# band4_1.net
KiCad netlist of a schematic drawn in EAGLE
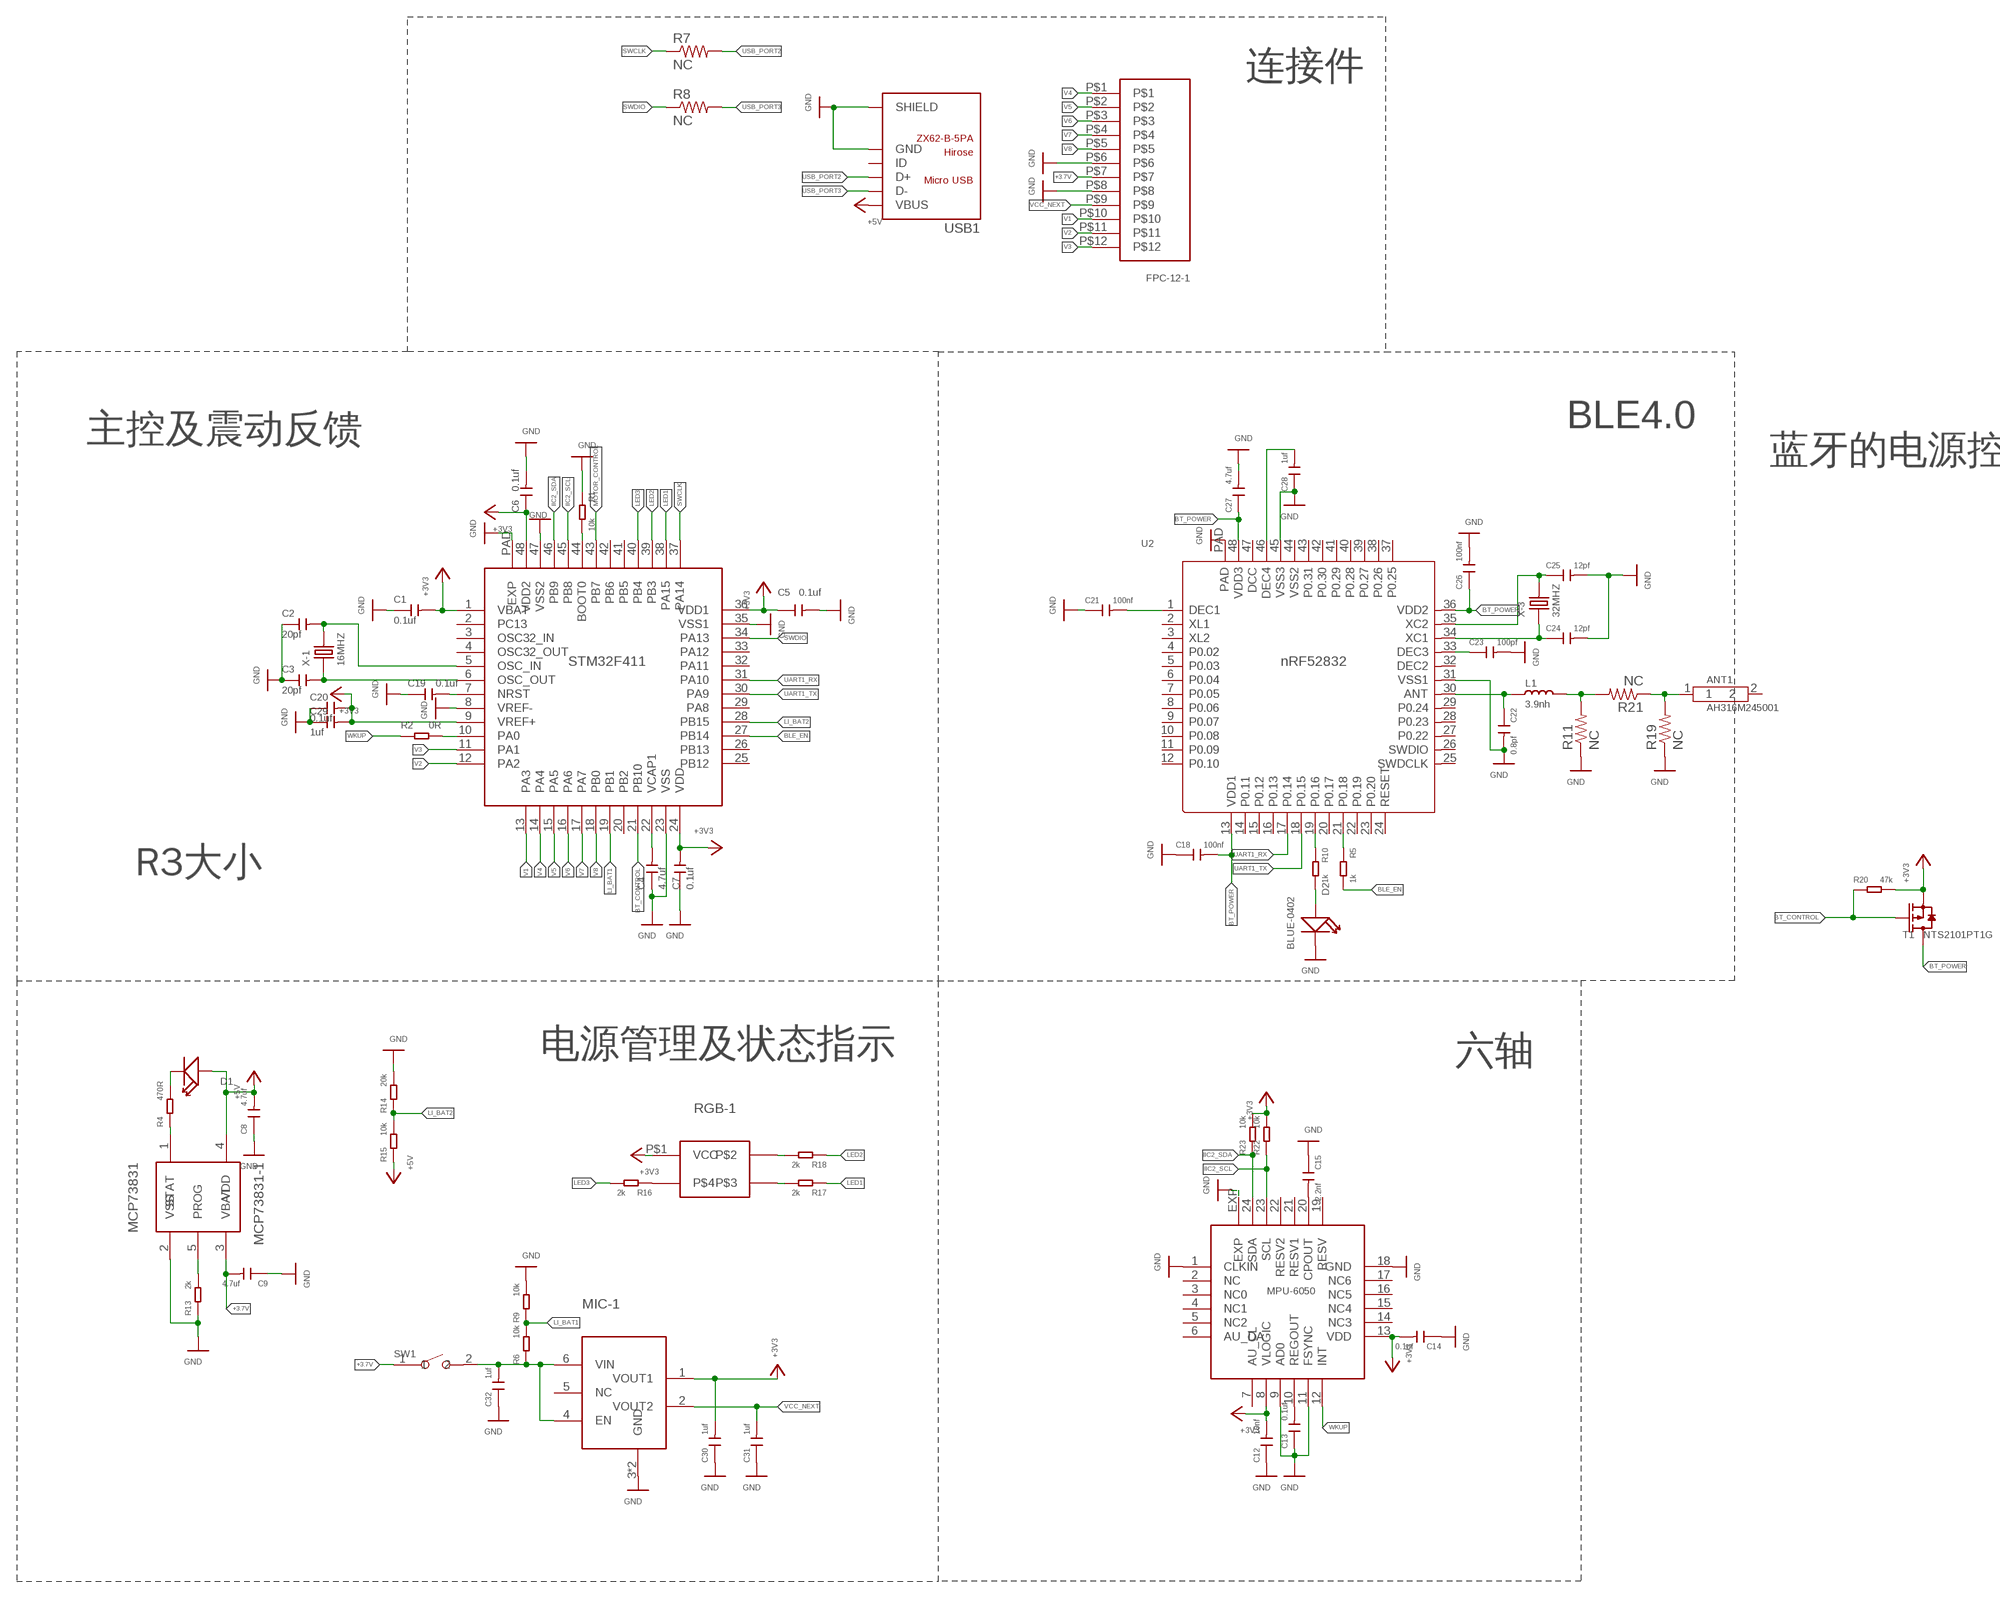
[diagram p0: schematic, sheet 1]

(export (version "E")
  (design (tool "Eeschema 10.0.6"))
  (components
    (comp (ref "ANT1")
      (value "AH316M245001")
      (footprint "eagle-import:ANT2-SMD-3.2X1.6X0.5MM")
      (fields (field (name "MPN") "AH316M245001-T"))
      (libsource (lib "eagle-import") (part "ANTENNA-2.4GHZ-AH316M245001-T"))
    )
    (comp (ref "C1")
      (value "0.1uf")
      (footprint "eagle-import:C0402")
      (fields (field (name "MPN") "CC0402BRNPO9BNR50"))
      (libsource (lib "eagle-import") (part "C(0402)"))
    )
    (comp (ref "C2")
      (value "20pf")
      (footprint "eagle-import:C0402")
      (fields (field (name "MPN") "CC0402BRNPO9BNR50"))
      (libsource (lib "eagle-import") (part "C(0402)"))
    )
    (comp (ref "C3")
      (value "20pf")
      (footprint "eagle-import:C0402")
      (fields (field (name "MPN") "CC0402BRNPO9BNR50"))
      (libsource (lib "eagle-import") (part "C(0402)"))
    )
    (comp (ref "C4")
      (value "4.7uf")
      (footprint "eagle-import:C0402")
      (fields (field (name "MPN") "CC0402BRNPO9BNR50"))
      (libsource (lib "eagle-import") (part "C(0402)"))
    )
    (comp (ref "C5")
      (value "0.1uf")
      (footprint "eagle-import:C0402")
      (fields (field (name "MPN") "CC0402BRNPO9BNR50"))
      (libsource (lib "eagle-import") (part "C(0402)"))
    )
    (comp (ref "C6")
      (value "0.1uf")
      (footprint "eagle-import:C0402")
      (fields (field (name "MPN") "CC0402BRNPO9BNR50"))
      (libsource (lib "eagle-import") (part "C(0402)"))
    )
    (comp (ref "C7")
      (value "0.1uf")
      (footprint "eagle-import:C0402")
      (fields (field (name "MPN") "CC0402BRNPO9BNR50"))
      (libsource (lib "eagle-import") (part "C(0402)"))
    )
    (comp (ref "C8")
      (value "4.7uf")
      (footprint "eagle-import:C0402")
      (fields (field (name "MPN") "CC0402BRNPO9BNR50"))
      (libsource (lib "eagle-import") (part "C(0402)"))
    )
    (comp (ref "C9")
      (value "4.7uf")
      (footprint "eagle-import:C0402")
      (fields (field (name "MPN") "CC0402BRNPO9BNR50"))
      (libsource (lib "eagle-import") (part "C(0402)"))
    )
    (comp (ref "C12")
      (value "10nf")
      (footprint "eagle-import:C0402")
      (fields (field (name "MPN") "CC0402BRNPO9BNR50"))
      (libsource (lib "eagle-import") (part "C(0402)"))
    )
    (comp (ref "C13")
      (value "0.1uf")
      (footprint "eagle-import:C0402")
      (fields (field (name "MPN") "CC0402BRNPO9BNR50"))
      (libsource (lib "eagle-import") (part "C(0402)"))
    )
    (comp (ref "C14")
      (value "0.1uf")
      (footprint "eagle-import:C0402")
      (fields (field (name "MPN") "CC0402BRNPO9BNR50"))
      (libsource (lib "eagle-import") (part "C(0402)"))
    )
    (comp (ref "C15")
      (value "2.2nf")
      (footprint "eagle-import:C0402")
      (fields (field (name "MPN") "CC0402BRNPO9BNR50"))
      (libsource (lib "eagle-import") (part "C(0402)"))
    )
    (comp (ref "C18")
      (value "100nf")
      (footprint "eagle-import:C0402")
      (fields (field (name "MPN") "CC0402BRNPO9BNR50"))
      (libsource (lib "eagle-import") (part "C(0402)"))
    )
    (comp (ref "C19")
      (value "0.1uf")
      (footprint "eagle-import:C0402")
      (fields (field (name "MPN") "CC0402BRNPO9BNR50"))
      (libsource (lib "eagle-import") (part "C(0402)"))
    )
    (comp (ref "C20")
      (value "0.1uf")
      (footprint "eagle-import:C0402")
      (fields (field (name "MPN") "CC0402BRNPO9BNR50"))
      (libsource (lib "eagle-import") (part "C(0402)"))
    )
    (comp (ref "C21")
      (value "100nf")
      (footprint "eagle-import:C0402")
      (fields (field (name "MPN") "CC0402BRNPO9BNR50"))
      (libsource (lib "eagle-import") (part "C(0402)"))
    )
    (comp (ref "C22")
      (value "0.8pf")
      (footprint "eagle-import:C0402")
      (fields (field (name "MPN") "CC0402BRNPO9BNR50"))
      (libsource (lib "eagle-import") (part "C(0402)"))
    )
    (comp (ref "C23")
      (value "100pf")
      (footprint "eagle-import:C0402")
      (fields (field (name "MPN") "CC0402BRNPO9BNR50"))
      (libsource (lib "eagle-import") (part "C(0402)"))
    )
    (comp (ref "C24")
      (value "12pf")
      (footprint "eagle-import:C0402")
      (fields (field (name "MPN") "CC0402BRNPO9BNR50"))
      (libsource (lib "eagle-import") (part "C(0402)"))
    )
    (comp (ref "C25")
      (value "12pf")
      (footprint "eagle-import:C0402")
      (fields (field (name "MPN") "CC0402BRNPO9BNR50"))
      (libsource (lib "eagle-import") (part "C(0402)"))
    )
    (comp (ref "C26")
      (value "100nf")
      (footprint "eagle-import:C0402")
      (fields (field (name "MPN") "CC0402BRNPO9BNR50"))
      (libsource (lib "eagle-import") (part "C(0402)"))
    )
    (comp (ref "C27")
      (value "4.7uf")
      (footprint "eagle-import:C0402")
      (fields (field (name "MPN") "CC0402BRNPO9BNR50"))
      (libsource (lib "eagle-import") (part "C(0402)"))
    )
    (comp (ref "C28")
      (value "1uf")
      (footprint "eagle-import:C0402")
      (fields (field (name "MPN") "CC0402BRNPO9BNR50"))
      (libsource (lib "eagle-import") (part "C(0402)"))
    )
    (comp (ref "C29")
      (value "1uf")
      (footprint "eagle-import:C0402")
      (fields (field (name "MPN") "CC0402BRNPO9BNR50"))
      (libsource (lib "eagle-import") (part "C(0402)"))
    )
    (comp (ref "C30")
      (value "1uf")
      (footprint "eagle-import:C0402")
      (fields (field (name "MPN") "CC0402BRNPO9BNR50"))
      (libsource (lib "eagle-import") (part "C(0402)"))
    )
    (comp (ref "C31")
      (value "1uf")
      (footprint "eagle-import:C0402")
      (fields (field (name "MPN") "CC0402BRNPO9BNR50"))
      (libsource (lib "eagle-import") (part "C(0402)"))
    )
    (comp (ref "C32")
      (value "1uf")
      (footprint "eagle-import:C0402")
      (fields (field (name "MPN") "CC0402BRNPO9BNR50"))
      (libsource (lib "eagle-import") (part "C(0402)"))
    )
    (comp (ref "D1")
      (value "LED-(0402)")
      (footprint "eagle-import:LED-0402")
      (fields (field (name "MPN") "BL-HB337A-AV-TRB"))
      (libsource (lib "eagle-import") (part "LED-(0402)"))
    )
    (comp (ref "D2")
      (value "BLUE-0402")
      (footprint "eagle-import:LED-0402")
      (fields (field (name "MPN") "BL-HB337A-AV-TRB"))
      (libsource (lib "eagle-import") (part "LED-(0402)"))
    )
    (comp (ref "FPC-12-1")
      (value "FPC-12")
      (footprint "eagle-import:FPC-12")
      (libsource (lib "eagle-import") (part "FPC-12"))
    )
    (comp (ref "L1")
      (value "3.9nh")
      (footprint "eagle-import:L0402")
      (libsource (lib "eagle-import") (part "INDUCTOR(0402)"))
    )
    (comp (ref "MCP73831-1")
      (value "MCP73831")
      (footprint "eagle-import:SOT23-5")
      (libsource (lib "eagle-import") (part "MCP73831"))
    )
    (comp (ref "MCU-1")
      (value "STM32F411")
      (footprint "eagle-import:QFN48G-0.5-7X7MM")
      (libsource (lib "eagle-import") (part "STM32F411"))
    )
    (comp (ref "MIC-1")
      (value "MIC5528")
      (footprint "eagle-import:THIN-DFN")
      (libsource (lib "eagle-import") (part "MIC5528"))
    )
    (comp (ref "MPU6050-1")
      (value "MPU-6050")
      (footprint "eagle-import:QFN24-4X4")
      (libsource (lib "eagle-import") (part "MPU-6050"))
    )
    (comp (ref "R1")
      (value "10k")
      (footprint "eagle-import:R0402")
      (fields (field (name "MPN") "RC0402JR-070RL"))
      (libsource (lib "eagle-import") (part "RES-(0402)"))
    )
    (comp (ref "R2")
      (value "0R")
      (footprint "eagle-import:R0402")
      (fields (field (name "MPN") "RC0402JR-070RL"))
      (libsource (lib "eagle-import") (part "RES-(0402)"))
    )
    (comp (ref "R4")
      (value "470R")
      (footprint "eagle-import:R0402")
      (fields (field (name "MPN") "RC0402JR-070RL"))
      (libsource (lib "eagle-import") (part "RES-(0402)"))
    )
    (comp (ref "R5")
      (value "1k")
      (footprint "eagle-import:R0402")
      (fields (field (name "MPN") "RC0402JR-070RL"))
      (libsource (lib "eagle-import") (part "RES-(0402)"))
    )
    (comp (ref "R6")
      (value "10k")
      (footprint "eagle-import:R0402")
      (fields (field (name "MPN") "RC0402JR-070RL"))
      (libsource (lib "eagle-import") (part "RES-(0402)"))
    )
    (comp (ref "R7")
      (value "NC")
      (footprint "eagle-import:0201")
      (libsource (lib "eagle-import") (part "R_0201"))
    )
    (comp (ref "R8")
      (value "NC")
      (footprint "eagle-import:0201")
      (libsource (lib "eagle-import") (part "R_0201"))
    )
    (comp (ref "R9")
      (value "10k")
      (footprint "eagle-import:R0402")
      (fields (field (name "MPN") "RC0402JR-070RL"))
      (libsource (lib "eagle-import") (part "RES-(0402)"))
    )
    (comp (ref "R10")
      (value "1k")
      (footprint "eagle-import:R0402")
      (fields (field (name "MPN") "RC0402JR-070RL"))
      (libsource (lib "eagle-import") (part "RES-(0402)"))
    )
    (comp (ref "R11")
      (value "NC")
      (footprint "eagle-import:0201")
      (libsource (lib "eagle-import") (part "R_0201"))
    )
    (comp (ref "R13")
      (value "2k")
      (footprint "eagle-import:R0402")
      (fields (field (name "MPN") "RC0402JR-070RL"))
      (libsource (lib "eagle-import") (part "RES-(0402)"))
    )
    (comp (ref "R14")
      (value "20k")
      (footprint "eagle-import:R0402")
      (fields (field (name "MPN") "RC0402JR-070RL"))
      (libsource (lib "eagle-import") (part "RES-(0402)"))
    )
    (comp (ref "R15")
      (value "10k")
      (footprint "eagle-import:R0402")
      (fields (field (name "MPN") "RC0402JR-070RL"))
      (libsource (lib "eagle-import") (part "RES-(0402)"))
    )
    (comp (ref "R16")
      (value "2k")
      (footprint "eagle-import:R0402")
      (fields (field (name "MPN") "RC0402JR-070RL"))
      (libsource (lib "eagle-import") (part "RES-(0402)"))
    )
    (comp (ref "R17")
      (value "2k")
      (footprint "eagle-import:R0402")
      (fields (field (name "MPN") "RC0402JR-070RL"))
      (libsource (lib "eagle-import") (part "RES-(0402)"))
    )
    (comp (ref "R18")
      (value "2k")
      (footprint "eagle-import:R0402")
      (fields (field (name "MPN") "RC0402JR-070RL"))
      (libsource (lib "eagle-import") (part "RES-(0402)"))
    )
    (comp (ref "R19")
      (value "NC")
      (footprint "eagle-import:0201")
      (libsource (lib "eagle-import") (part "R_0201"))
    )
    (comp (ref "R20")
      (value "47k")
      (footprint "eagle-import:R0402")
      (fields (field (name "MPN") "RC0402JR-070RL"))
      (libsource (lib "eagle-import") (part "RES-(0402)"))
    )
    (comp (ref "R21")
      (value "NC")
      (footprint "eagle-import:0201")
      (libsource (lib "eagle-import") (part "R_0201"))
    )
    (comp (ref "R22")
      (value "10k")
      (footprint "eagle-import:R0402")
      (fields (field (name "MPN") "RC0402JR-070RL"))
      (libsource (lib "eagle-import") (part "RES-(0402)"))
    )
    (comp (ref "R23")
      (value "10k")
      (footprint "eagle-import:R0402")
      (fields (field (name "MPN") "RC0402JR-070RL"))
      (libsource (lib "eagle-import") (part "RES-(0402)"))
    )
    (comp (ref "RGB-1")
      (value "RGB-LED")
      (footprint "eagle-import:RGB-LED")
      (libsource (lib "eagle-import") (part "RGB-LED"))
    )
    (comp (ref "SW1")
      (value "SMD-BUTTON(2P-6.0X3.0X2.5MM)-DHT-1163S")
      (footprint "eagle-import:SW2-4.0-6.0X3.0X2.5MM")
      (libsource (lib "eagle-import") (part "SMD-BUTTON(2P-6.0X3.0X2.5MM)-DHT-1163S"))
    )
    (comp (ref "T1")
      (value "NTS2101PT1G")
      (footprint "eagle-import:SC70")
      (libsource (lib "eagle-import") (part "NTS2101PT1G"))
    )
    (comp (ref "U2")
      (value "RF-51822")
      (footprint "eagle-import:QFN48G-0.4-6X6MM")
      (libsource (lib "eagle-import") (part "IC-NRF-52832(QFN48)"))
    )
    (comp (ref "USB1")
      (value "ZX62-B-5PA")
      (footprint "eagle-import:MICRO-USB5+6P-SMD-0.65-AB")
      (libsource (lib "eagle-import") (part "MICRO-USB-SMD(ZX62-B-5PA)"))
    )
    (comp (ref "X-1")
      (value "16MHZ")
      (footprint "eagle-import:16MHZ")
      (libsource (lib "eagle-import") (part "16MHZ"))
    )
    (comp (ref "X-3")
      (value "32MHZ")
      (footprint "eagle-import:16MHZ")
      (libsource (lib "eagle-import") (part "16MHZ"))
    )
  )
  (nets
    (net (code "1") (name "+3.7V") (class "Default")
      (node (ref "C9") (pin "2") (pinfunction "2_2") (pintype "passive"))
      (node (ref "FPC-12-1") (pin "P$7") (pinfunction "P$7_P$7") (pintype "bidirectional"))
      (node (ref "MCP73831-1") (pin "3") (pinfunction "VBAT_3") (pintype "bidirectional"))
      (node (ref "SW1") (pin "1") (pinfunction "1_1") (pintype "bidirectional"))
    )
    (net (code "2") (name "+3V3") (class "Default")
      (node (ref "C1") (pin "2") (pinfunction "2_2") (pintype "passive"))
      (node (ref "C12") (pin "2") (pinfunction "2_2") (pintype "passive"))
      (node (ref "C14") (pin "2") (pinfunction "2_2") (pintype "passive"))
      (node (ref "C20") (pin "2") (pinfunction "2_2") (pintype "passive"))
      (node (ref "C29") (pin "2") (pinfunction "2_2") (pintype "passive"))
      (node (ref "C30") (pin "2") (pinfunction "2_2") (pintype "passive"))
      (node (ref "C5") (pin "1") (pinfunction "1_1") (pintype "passive"))
      (node (ref "C6") (pin "1") (pinfunction "1_1") (pintype "passive"))
      (node (ref "C7") (pin "2") (pinfunction "2_2") (pintype "passive"))
      (node (ref "MCU-1") (pin "1") (pinfunction "VBAT_1") (pintype "bidirectional"))
      (node (ref "MCU-1") (pin "24") (pinfunction "VDD_24") (pintype "bidirectional"))
      (node (ref "MCU-1") (pin "36") (pinfunction "VDD1_36") (pintype "bidirectional"))
      (node (ref "MCU-1") (pin "48") (pinfunction "VDD2_48") (pintype "bidirectional"))
      (node (ref "MCU-1") (pin "9") (pinfunction "VREF+_9") (pintype "bidirectional"))
      (node (ref "MIC-1") (pin "1") (pinfunction "VOUT1_1") (pintype "bidirectional"))
      (node (ref "MPU6050-1") (pin "13") (pinfunction "VDD_13") (pintype "bidirectional"))
      (node (ref "MPU6050-1") (pin "8") (pinfunction "VLOGIC_8") (pintype "bidirectional"))
      (node (ref "R20") (pin "2") (pinfunction "2_2") (pintype "passive"))
      (node (ref "R22") (pin "2") (pinfunction "2_2") (pintype "passive"))
      (node (ref "R23") (pin "2") (pinfunction "2_2") (pintype "passive"))
      (node (ref "RGB-1") (pin "P$1") (pinfunction "VCC_P$1") (pintype "bidirectional"))
      (node (ref "T1") (pin "2") (pinfunction "S_2") (pintype "passive"))
    )
    (net (code "3") (name "+5V") (class "Default")
      (node (ref "C8") (pin "2") (pinfunction "2_2") (pintype "passive"))
      (node (ref "D1") (pin "+") (pinfunction "+_+") (pintype "passive"))
      (node (ref "MCP73831-1") (pin "4") (pinfunction "VDD_4") (pintype "bidirectional"))
      (node (ref "R15") (pin "1") (pinfunction "1_1") (pintype "passive"))
      (node (ref "USB1") (pin "1") (pinfunction "VBUS_1") (pintype "power_in"))
    )
    (net (code "4") (name "BLE_EN") (class "Default")
      (node (ref "MCU-1") (pin "27") (pinfunction "PB14_27") (pintype "bidirectional"))
      (node (ref "R5") (pin "2") (pinfunction "2_2") (pintype "passive"))
    )
    (net (code "5") (name "BT_CONTROL") (class "Default")
      (node (ref "MCU-1") (pin "21") (pinfunction "PB10_21") (pintype "bidirectional"))
      (node (ref "R20") (pin "1") (pinfunction "1_1") (pintype "passive"))
      (node (ref "T1") (pin "1") (pinfunction "G_1") (pintype "passive"))
    )
    (net (code "6") (name "BT_POWER") (class "Default")
      (node (ref "C18") (pin "2") (pinfunction "2_2") (pintype "passive"))
      (node (ref "C26") (pin "1") (pinfunction "1_1") (pintype "passive"))
      (node (ref "C27") (pin "1") (pinfunction "1_1") (pintype "passive"))
      (node (ref "T1") (pin "3") (pinfunction "D_3") (pintype "passive"))
      (node (ref "U2") (pin "13") (pinfunction "VDD1_13") (pintype "bidirectional"))
      (node (ref "U2") (pin "36") (pinfunction "VDD2_36") (pintype "bidirectional"))
      (node (ref "U2") (pin "48") (pinfunction "VDD3_48") (pintype "bidirectional"))
    )
    (net (code "7") (name "GND") (class "Default")
      (node (ref "C1") (pin "1") (pinfunction "1_1") (pintype "passive"))
      (node (ref "C12") (pin "1") (pinfunction "1_1") (pintype "passive"))
      (node (ref "C13") (pin "1") (pinfunction "1_1") (pintype "passive"))
      (node (ref "C14") (pin "1") (pinfunction "1_1") (pintype "passive"))
      (node (ref "C15") (pin "1") (pinfunction "1_1") (pintype "passive"))
      (node (ref "C18") (pin "1") (pinfunction "1_1") (pintype "passive"))
      (node (ref "C19") (pin "1") (pinfunction "1_1") (pintype "passive"))
      (node (ref "C2") (pin "1") (pinfunction "1_1") (pintype "passive"))
      (node (ref "C20") (pin "1") (pinfunction "1_1") (pintype "passive"))
      (node (ref "C21") (pin "1") (pinfunction "1_1") (pintype "passive"))
      (node (ref "C22") (pin "2") (pinfunction "2_2") (pintype "passive"))
      (node (ref "C23") (pin "2") (pinfunction "2_2") (pintype "passive"))
      (node (ref "C24") (pin "2") (pinfunction "2_2") (pintype "passive"))
      (node (ref "C25") (pin "2") (pinfunction "2_2") (pintype "passive"))
      (node (ref "C26") (pin "2") (pinfunction "2_2") (pintype "passive"))
      (node (ref "C27") (pin "2") (pinfunction "2_2") (pintype "passive"))
      (node (ref "C28") (pin "1") (pinfunction "1_1") (pintype "passive"))
      (node (ref "C29") (pin "1") (pinfunction "1_1") (pintype "passive"))
      (node (ref "C3") (pin "1") (pinfunction "1_1") (pintype "passive"))
      (node (ref "C30") (pin "1") (pinfunction "1_1") (pintype "passive"))
      (node (ref "C31") (pin "1") (pinfunction "1_1") (pintype "passive"))
      (node (ref "C32") (pin "1") (pinfunction "1_1") (pintype "passive"))
      (node (ref "C4") (pin "1") (pinfunction "1_1") (pintype "passive"))
      (node (ref "C5") (pin "2") (pinfunction "2_2") (pintype "passive"))
      (node (ref "C6") (pin "2") (pinfunction "2_2") (pintype "passive"))
      (node (ref "C7") (pin "1") (pinfunction "1_1") (pintype "passive"))
      (node (ref "C8") (pin "1") (pinfunction "1_1") (pintype "passive"))
      (node (ref "C9") (pin "1") (pinfunction "1_1") (pintype "passive"))
      (node (ref "D2") (pin "-") (pinfunction "-_-") (pintype "passive"))
      (node (ref "FPC-12-1") (pin "P$6") (pinfunction "P$6_P$6") (pintype "bidirectional"))
      (node (ref "FPC-12-1") (pin "P$8") (pinfunction "P$8_P$8") (pintype "bidirectional"))
      (node (ref "MCP73831-1") (pin "2") (pinfunction "VSS_2") (pintype "bidirectional"))
      (node (ref "MCU-1") (pin "23") (pinfunction "VSS_23") (pintype "bidirectional"))
      (node (ref "MCU-1") (pin "35") (pinfunction "VSS1_35") (pintype "bidirectional"))
      (node (ref "MCU-1") (pin "47") (pinfunction "VSS2_47") (pintype "bidirectional"))
      (node (ref "MCU-1") (pin "8") (pinfunction "VREF-_8") (pintype "bidirectional"))
      (node (ref "MCU-1") (pin "PAD") (pinfunction "EXP_PAD") (pintype "bidirectional"))
      (node (ref "MIC-1") (pin "3") (pinfunction "GND_3") (pintype "bidirectional"))
      (node (ref "MIC-1") (pin "7") (pinfunction "GND_7") (pintype "bidirectional"))
      (node (ref "MPU6050-1") (pin "1") (pinfunction "CLKIN_1") (pintype "bidirectional"))
      (node (ref "MPU6050-1") (pin "11") (pinfunction "FSYNC_11") (pintype "bidirectional"))
      (node (ref "MPU6050-1") (pin "18") (pinfunction "GND_18") (pintype "bidirectional"))
      (node (ref "MPU6050-1") (pin "9") (pinfunction "AD0_9") (pintype "bidirectional"))
      (node (ref "MPU6050-1") (pin "EXP") (pinfunction "EXP_EXP") (pintype "bidirectional"))
      (node (ref "R1") (pin "1") (pinfunction "1_1") (pintype "passive"))
      (node (ref "R11") (pin "1") (pinfunction "1_1") (pintype "passive"))
      (node (ref "R13") (pin "1") (pinfunction "1_1") (pintype "passive"))
      (node (ref "R14") (pin "2") (pinfunction "2_2") (pintype "passive"))
      (node (ref "R19") (pin "1") (pinfunction "1_1") (pintype "passive"))
      (node (ref "R9") (pin "2") (pinfunction "2_2") (pintype "passive"))
      (node (ref "U2") (pin "31") (pinfunction "VSS1_31") (pintype "bidirectional"))
      (node (ref "U2") (pin "45") (pinfunction "VSS3_45") (pintype "bidirectional"))
      (node (ref "U2") (pin "PAD") (pinfunction "PAD_PAD") (pintype "bidirectional"))
      (node (ref "USB1") (pin "5") (pinfunction "GND_5") (pintype "power_in"))
      (node (ref "USB1") (pin "P1") (pinfunction "SHIELD_P1") (pintype "power_in"))
      (node (ref "USB1") (pin "P2") (pinfunction "SHIELD_P2") (pintype "power_in"))
      (node (ref "USB1") (pin "P3") (pinfunction "SHIELD_P3") (pintype "power_in"))
      (node (ref "USB1") (pin "P4") (pinfunction "SHIELD_P4") (pintype "power_in"))
      (node (ref "USB1") (pin "P5") (pinfunction "SHIELD_P5") (pintype "power_in"))
      (node (ref "USB1") (pin "P6") (pinfunction "SHIELD_P6") (pintype "power_in"))
    )
    (net (code "8") (name "IIC2_SCL") (class "Default")
      (node (ref "MCU-1") (pin "45") (pinfunction "PB8_45") (pintype "bidirectional"))
      (node (ref "MPU6050-1") (pin "23") (pinfunction "SCL_23") (pintype "bidirectional"))
      (node (ref "R22") (pin "1") (pinfunction "1_1") (pintype "passive"))
    )
    (net (code "9") (name "IIC2_SDA") (class "Default")
      (node (ref "MCU-1") (pin "46") (pinfunction "PB9_46") (pintype "bidirectional"))
      (node (ref "MPU6050-1") (pin "24") (pinfunction "SDA_24") (pintype "bidirectional"))
      (node (ref "R23") (pin "1") (pinfunction "1_1") (pintype "passive"))
    )
    (net (code "10") (name "LED1") (class "Default")
      (node (ref "MCU-1") (pin "38") (pinfunction "PA15_38") (pintype "bidirectional"))
      (node (ref "R17") (pin "1") (pinfunction "1_1") (pintype "passive"))
    )
    (net (code "11") (name "LED2") (class "Default")
      (node (ref "MCU-1") (pin "39") (pinfunction "PB3_39") (pintype "bidirectional"))
      (node (ref "R18") (pin "1") (pinfunction "1_1") (pintype "passive"))
    )
    (net (code "12") (name "LED3") (class "Default")
      (node (ref "MCU-1") (pin "40") (pinfunction "PB4_40") (pintype "bidirectional"))
      (node (ref "R16") (pin "2") (pinfunction "2_2") (pintype "passive"))
    )
    (net (code "13") (name "LI_BAT1") (class "Default")
      (node (ref "MCU-1") (pin "19") (pinfunction "PB1_19") (pintype "bidirectional"))
      (node (ref "R6") (pin "2") (pinfunction "2_2") (pintype "passive"))
      (node (ref "R9") (pin "1") (pinfunction "1_1") (pintype "passive"))
    )
    (net (code "14") (name "LI_BAT2") (class "Default")
      (node (ref "MCU-1") (pin "28") (pinfunction "PB15_28") (pintype "bidirectional"))
      (node (ref "R14") (pin "1") (pinfunction "1_1") (pintype "passive"))
      (node (ref "R15") (pin "2") (pinfunction "2_2") (pintype "passive"))
    )
    (net (code "15") (name "MOTOR_CONTROL") (class "Default")
      (node (ref "MCU-1") (pin "43") (pinfunction "PB7_43") (pintype "bidirectional"))
    )
    (net (code "16") (name "Net-(ANT1-Pad1)") (class "Default")
      (node (ref "ANT1") (pin "1") (pinfunction "1_1") (pintype "bidirectional"))
      (node (ref "R19") (pin "2") (pinfunction "2_2") (pintype "passive"))
      (node (ref "R21") (pin "1") (pinfunction "1_1") (pintype "passive"))
    )
    (net (code "17") (name "Net-(D1-Pad-)") (class "Default")
      (node (ref "D1") (pin "-") (pinfunction "-_-") (pintype "passive"))
      (node (ref "R4") (pin "2") (pinfunction "2_2") (pintype "passive"))
    )
    (net (code "18") (name "Net-(D2-Pad+)") (class "Default")
      (node (ref "D2") (pin "+") (pinfunction "+_+") (pintype "passive"))
      (node (ref "R10") (pin "2") (pinfunction "2_2") (pintype "passive"))
    )
    (net (code "19") (name "Net-(L1-Pad2)") (class "Default")
      (node (ref "L1") (pin "2") (pinfunction "2_2") (pintype "passive"))
      (node (ref "R11") (pin "2") (pinfunction "2_2") (pintype "passive"))
      (node (ref "R21") (pin "2") (pinfunction "2_2") (pintype "passive"))
    )
    (net (code "20") (name "Net-(MCP73831-1-PROG)") (class "Default")
      (node (ref "MCP73831-1") (pin "5") (pinfunction "PROG_5") (pintype "bidirectional"))
      (node (ref "R13") (pin "2") (pinfunction "2_2") (pintype "passive"))
    )
    (net (code "21") (name "Net-(MCP73831-1-STAT)") (class "Default")
      (node (ref "MCP73831-1") (pin "1") (pinfunction "STAT_1") (pintype "bidirectional"))
      (node (ref "R4") (pin "1") (pinfunction "1_1") (pintype "passive"))
    )
    (net (code "22") (name "Net-(MCU-1-BOOT0)") (class "Default")
      (node (ref "MCU-1") (pin "44") (pinfunction "BOOT0_44") (pintype "bidirectional"))
      (node (ref "R1") (pin "2") (pinfunction "2_2") (pintype "passive"))
    )
    (net (code "23") (name "Net-(MCU-1-NRST)") (class "Default")
      (node (ref "C19") (pin "2") (pinfunction "2_2") (pintype "passive"))
      (node (ref "MCU-1") (pin "7") (pinfunction "NRST_7") (pintype "bidirectional"))
    )
    (net (code "24") (name "Net-(MCU-1-OSC_IN)") (class "Default")
      (node (ref "C2") (pin "2") (pinfunction "2_2") (pintype "passive"))
      (node (ref "MCU-1") (pin "5") (pinfunction "OSC_IN_5") (pintype "bidirectional"))
      (node (ref "X-1") (pin "3") (pinfunction "2_3") (pintype "passive"))
    )
    (net (code "25") (name "Net-(MCU-1-OSC_OUT)") (class "Default")
      (node (ref "C3") (pin "2") (pinfunction "2_2") (pintype "passive"))
      (node (ref "MCU-1") (pin "6") (pinfunction "OSC_OUT_6") (pintype "bidirectional"))
      (node (ref "X-1") (pin "1") (pinfunction "1_1") (pintype "passive"))
    )
    (net (code "26") (name "Net-(MCU-1-PA0)") (class "Default")
      (node (ref "MCU-1") (pin "10") (pinfunction "PA0_10") (pintype "bidirectional"))
      (node (ref "R2") (pin "2") (pinfunction "2_2") (pintype "passive"))
    )
    (net (code "27") (name "Net-(MCU-1-VCAP1)") (class "Default")
      (node (ref "C4") (pin "2") (pinfunction "2_2") (pintype "passive"))
      (node (ref "MCU-1") (pin "22") (pinfunction "VCAP1_22") (pintype "bidirectional"))
    )
    (net (code "28") (name "Net-(MIC-1-EN)") (class "Default")
      (node (ref "C32") (pin "2") (pinfunction "2_2") (pintype "passive"))
      (node (ref "MIC-1") (pin "4") (pinfunction "EN_4") (pintype "bidirectional"))
      (node (ref "MIC-1") (pin "6") (pinfunction "VIN_6") (pintype "bidirectional"))
      (node (ref "R6") (pin "1") (pinfunction "1_1") (pintype "passive"))
      (node (ref "SW1") (pin "2") (pinfunction "2_2") (pintype "bidirectional"))
    )
    (net (code "29") (name "Net-(MPU6050-1-CPOUT)") (class "Default")
      (node (ref "C15") (pin "2") (pinfunction "2_2") (pintype "passive"))
      (node (ref "MPU6050-1") (pin "20") (pinfunction "CPOUT_20") (pintype "bidirectional"))
    )
    (net (code "30") (name "Net-(MPU6050-1-REGOUT)") (class "Default")
      (node (ref "C13") (pin "2") (pinfunction "2_2") (pintype "passive"))
      (node (ref "MPU6050-1") (pin "10") (pinfunction "REGOUT_10") (pintype "bidirectional"))
    )
    (net (code "31") (name "Net-(R16-Pad1)") (class "Default")
      (node (ref "R16") (pin "1") (pinfunction "1_1") (pintype "passive"))
      (node (ref "RGB-1") (pin "P$4") (pinfunction "P$4_P$4") (pintype "bidirectional"))
    )
    (net (code "32") (name "Net-(R17-Pad2)") (class "Default")
      (node (ref "R17") (pin "2") (pinfunction "2_2") (pintype "passive"))
      (node (ref "RGB-1") (pin "P$3") (pinfunction "P$3_P$3") (pintype "bidirectional"))
    )
    (net (code "33") (name "Net-(R18-Pad2)") (class "Default")
      (node (ref "R18") (pin "2") (pinfunction "2_2") (pintype "passive"))
      (node (ref "RGB-1") (pin "P$2") (pinfunction "P$2_P$2") (pintype "bidirectional"))
    )
    (net (code "34") (name "Net-(U2-ANT)") (class "Default")
      (node (ref "C22") (pin "1") (pinfunction "1_1") (pintype "passive"))
      (node (ref "L1") (pin "1") (pinfunction "1_1") (pintype "passive"))
      (node (ref "U2") (pin "30") (pinfunction "ANT_30") (pintype "bidirectional"))
    )
    (net (code "35") (name "Net-(U2-DEC1)") (class "Default")
      (node (ref "C21") (pin "2") (pinfunction "2_2") (pintype "passive"))
      (node (ref "U2") (pin "1") (pinfunction "DEC1_1") (pintype "bidirectional"))
    )
    (net (code "36") (name "Net-(U2-DEC3)") (class "Default")
      (node (ref "C23") (pin "1") (pinfunction "1_1") (pintype "passive"))
      (node (ref "U2") (pin "33") (pinfunction "DEC3_33") (pintype "bidirectional"))
    )
    (net (code "37") (name "Net-(U2-DEC4)") (class "Default")
      (node (ref "C28") (pin "2") (pinfunction "2_2") (pintype "passive"))
      (node (ref "U2") (pin "46") (pinfunction "DEC4_46") (pintype "bidirectional"))
    )
    (net (code "38") (name "Net-(U2-P0.16)") (class "Default")
      (node (ref "R10") (pin "1") (pinfunction "1_1") (pintype "passive"))
      (node (ref "U2") (pin "19") (pinfunction "P0.16_19") (pintype "bidirectional"))
    )
    (net (code "39") (name "Net-(U2-P0.18)") (class "Default")
      (node (ref "R5") (pin "1") (pinfunction "1_1") (pintype "passive"))
      (node (ref "U2") (pin "21") (pinfunction "P0.18_21") (pintype "bidirectional"))
    )
    (net (code "40") (name "Net-(U2-XC1)") (class "Default")
      (node (ref "C24") (pin "1") (pinfunction "1_1") (pintype "passive"))
      (node (ref "U2") (pin "34") (pinfunction "XC1_34") (pintype "bidirectional"))
      (node (ref "X-3") (pin "1") (pinfunction "1_1") (pintype "passive"))
    )
    (net (code "41") (name "Net-(U2-XC2)") (class "Default")
      (node (ref "C25") (pin "1") (pinfunction "1_1") (pintype "passive"))
      (node (ref "U2") (pin "35") (pinfunction "XC2_35") (pintype "bidirectional"))
      (node (ref "X-3") (pin "3") (pinfunction "2_3") (pintype "passive"))
    )
    (net (code "42") (name "SWCLK") (class "Default")
      (node (ref "MCU-1") (pin "37") (pinfunction "PA14_37") (pintype "bidirectional"))
      (node (ref "R7") (pin "1") (pinfunction "1_1") (pintype "passive"))
    )
    (net (code "43") (name "SWDIO") (class "Default")
      (node (ref "MCU-1") (pin "34") (pinfunction "PA13_34") (pintype "bidirectional"))
      (node (ref "R8") (pin "1") (pinfunction "1_1") (pintype "passive"))
    )
    (net (code "44") (name "UART1_RX") (class "Default")
      (node (ref "MCU-1") (pin "31") (pinfunction "PA10_31") (pintype "bidirectional"))
      (node (ref "U2") (pin "17") (pinfunction "P0.14_17") (pintype "bidirectional"))
    )
    (net (code "45") (name "UART1_TX") (class "Default")
      (node (ref "MCU-1") (pin "30") (pinfunction "PA9_30") (pintype "bidirectional"))
      (node (ref "U2") (pin "18") (pinfunction "P0.15_18") (pintype "bidirectional"))
    )
    (net (code "46") (name "USB_PORT2") (class "Default")
      (node (ref "R7") (pin "2") (pinfunction "2_2") (pintype "passive"))
      (node (ref "USB1") (pin "3") (pinfunction "D+_3") (pintype "bidirectional"))
    )
    (net (code "47") (name "USB_PORT3") (class "Default")
      (node (ref "R8") (pin "2") (pinfunction "2_2") (pintype "passive"))
      (node (ref "USB1") (pin "2") (pinfunction "D-_2") (pintype "bidirectional"))
    )
    (net (code "48") (name "V1") (class "Default")
      (node (ref "FPC-12-1") (pin "P$10") (pinfunction "P$10_P$10") (pintype "bidirectional"))
      (node (ref "MCU-1") (pin "13") (pinfunction "PA3_13") (pintype "bidirectional"))
    )
    (net (code "49") (name "V2") (class "Default")
      (node (ref "FPC-12-1") (pin "P$11") (pinfunction "P$11_P$11") (pintype "bidirectional"))
      (node (ref "MCU-1") (pin "12") (pinfunction "PA2_12") (pintype "bidirectional"))
    )
    (net (code "50") (name "V3") (class "Default")
      (node (ref "FPC-12-1") (pin "P$12") (pinfunction "P$12_P$12") (pintype "bidirectional"))
      (node (ref "MCU-1") (pin "11") (pinfunction "PA1_11") (pintype "bidirectional"))
    )
    (net (code "51") (name "V4") (class "Default")
      (node (ref "FPC-12-1") (pin "P$1") (pinfunction "P$1_P$1") (pintype "bidirectional"))
      (node (ref "MCU-1") (pin "14") (pinfunction "PA4_14") (pintype "bidirectional"))
    )
    (net (code "52") (name "V5") (class "Default")
      (node (ref "FPC-12-1") (pin "P$2") (pinfunction "P$2_P$2") (pintype "bidirectional"))
      (node (ref "MCU-1") (pin "15") (pinfunction "PA5_15") (pintype "bidirectional"))
    )
    (net (code "53") (name "V6") (class "Default")
      (node (ref "FPC-12-1") (pin "P$3") (pinfunction "P$3_P$3") (pintype "bidirectional"))
      (node (ref "MCU-1") (pin "16") (pinfunction "PA6_16") (pintype "bidirectional"))
    )
    (net (code "54") (name "V7") (class "Default")
      (node (ref "FPC-12-1") (pin "P$4") (pinfunction "P$4_P$4") (pintype "bidirectional"))
      (node (ref "MCU-1") (pin "17") (pinfunction "PA7_17") (pintype "bidirectional"))
    )
    (net (code "55") (name "V8") (class "Default")
      (node (ref "FPC-12-1") (pin "P$5") (pinfunction "P$5_P$5") (pintype "bidirectional"))
      (node (ref "MCU-1") (pin "18") (pinfunction "PB0_18") (pintype "bidirectional"))
    )
    (net (code "56") (name "VCC_NEXT") (class "Default")
      (node (ref "C31") (pin "2") (pinfunction "2_2") (pintype "passive"))
      (node (ref "FPC-12-1") (pin "P$9") (pinfunction "P$9_P$9") (pintype "bidirectional"))
      (node (ref "MIC-1") (pin "2") (pinfunction "VOUT2_2") (pintype "bidirectional"))
    )
    (net (code "57") (name "WKUP") (class "Default")
      (node (ref "MPU6050-1") (pin "12") (pinfunction "INT_12") (pintype "bidirectional"))
      (node (ref "R2") (pin "1") (pinfunction "1_1") (pintype "passive"))
    )
    (net (code "58") (name "unconnected-(ANT1-Pad2)") (class "Default")
      (node (ref "ANT1") (pin "2") (pinfunction "2_2") (pintype "bidirectional"))
    )
    (net (code "59") (name "unconnected-(MCU-1-OSC32_IN-Pad3)") (class "Default")
      (node (ref "MCU-1") (pin "3") (pinfunction "OSC32_IN_3") (pintype "bidirectional"))
    )
    (net (code "60") (name "unconnected-(MCU-1-OSC32_OUT-Pad4)") (class "Default")
      (node (ref "MCU-1") (pin "4") (pinfunction "OSC32_OUT_4") (pintype "bidirectional"))
    )
    (net (code "61") (name "unconnected-(MCU-1-PA8-Pad29)") (class "Default")
      (node (ref "MCU-1") (pin "29") (pinfunction "PA8_29") (pintype "bidirectional"))
    )
    (net (code "62") (name "unconnected-(MCU-1-PA11-Pad32)") (class "Default")
      (node (ref "MCU-1") (pin "32") (pinfunction "PA11_32") (pintype "bidirectional"))
    )
    (net (code "63") (name "unconnected-(MCU-1-PA12-Pad33)") (class "Default")
      (node (ref "MCU-1") (pin "33") (pinfunction "PA12_33") (pintype "bidirectional"))
    )
    (net (code "64") (name "unconnected-(MCU-1-PB2-Pad20)") (class "Default")
      (node (ref "MCU-1") (pin "20") (pinfunction "PB2_20") (pintype "bidirectional"))
    )
    (net (code "65") (name "unconnected-(MCU-1-PB5-Pad41)") (class "Default")
      (node (ref "MCU-1") (pin "41") (pinfunction "PB5_41") (pintype "bidirectional"))
    )
    (net (code "66") (name "unconnected-(MCU-1-PB6-Pad42)") (class "Default")
      (node (ref "MCU-1") (pin "42") (pinfunction "PB6_42") (pintype "bidirectional"))
    )
    (net (code "67") (name "unconnected-(MCU-1-PB12-Pad25)") (class "Default")
      (node (ref "MCU-1") (pin "25") (pinfunction "PB12_25") (pintype "bidirectional"))
    )
    (net (code "68") (name "unconnected-(MCU-1-PB13-Pad26)") (class "Default")
      (node (ref "MCU-1") (pin "26") (pinfunction "PB13_26") (pintype "bidirectional"))
    )
    (net (code "69") (name "unconnected-(MCU-1-PC13-Pad2)") (class "Default")
      (node (ref "MCU-1") (pin "2") (pinfunction "PC13_2") (pintype "bidirectional"))
    )
    (net (code "70") (name "unconnected-(MIC-1-NC-Pad5)") (class "Default")
      (node (ref "MIC-1") (pin "5") (pinfunction "NC_5") (pintype "bidirectional"))
    )
    (net (code "71") (name "unconnected-(MPU6050-1-AU_CL-Pad7)") (class "Default")
      (node (ref "MPU6050-1") (pin "7") (pinfunction "AU_CL_7") (pintype "bidirectional"))
    )
    (net (code "72") (name "unconnected-(MPU6050-1-AU_DA-Pad6)") (class "Default")
      (node (ref "MPU6050-1") (pin "6") (pinfunction "AU_DA_6") (pintype "bidirectional"))
    )
    (net (code "73") (name "unconnected-(MPU6050-1-NC-Pad2)") (class "Default")
      (node (ref "MPU6050-1") (pin "2") (pinfunction "NC_2") (pintype "bidirectional"))
    )
    (net (code "74") (name "unconnected-(MPU6050-1-NC0-Pad3)") (class "Default")
      (node (ref "MPU6050-1") (pin "3") (pinfunction "NC0_3") (pintype "bidirectional"))
    )
    (net (code "75") (name "unconnected-(MPU6050-1-NC1-Pad4)") (class "Default")
      (node (ref "MPU6050-1") (pin "4") (pinfunction "NC1_4") (pintype "bidirectional"))
    )
    (net (code "76") (name "unconnected-(MPU6050-1-NC2-Pad5)") (class "Default")
      (node (ref "MPU6050-1") (pin "5") (pinfunction "NC2_5") (pintype "bidirectional"))
    )
    (net (code "77") (name "unconnected-(MPU6050-1-NC3-Pad14)") (class "Default")
      (node (ref "MPU6050-1") (pin "14") (pinfunction "NC3_14") (pintype "bidirectional"))
    )
    (net (code "78") (name "unconnected-(MPU6050-1-NC4-Pad15)") (class "Default")
      (node (ref "MPU6050-1") (pin "15") (pinfunction "NC4_15") (pintype "bidirectional"))
    )
    (net (code "79") (name "unconnected-(MPU6050-1-NC5-Pad16)") (class "Default")
      (node (ref "MPU6050-1") (pin "16") (pinfunction "NC5_16") (pintype "bidirectional"))
    )
    (net (code "80") (name "unconnected-(MPU6050-1-NC6-Pad17)") (class "Default")
      (node (ref "MPU6050-1") (pin "17") (pinfunction "NC6_17") (pintype "bidirectional"))
    )
    (net (code "81") (name "unconnected-(MPU6050-1-RESV-Pad19)") (class "Default")
      (node (ref "MPU6050-1") (pin "19") (pinfunction "RESV_19") (pintype "bidirectional"))
    )
    (net (code "82") (name "unconnected-(MPU6050-1-RESV1-Pad21)") (class "Default")
      (node (ref "MPU6050-1") (pin "21") (pinfunction "RESV1_21") (pintype "bidirectional"))
    )
    (net (code "83") (name "unconnected-(MPU6050-1-RESV2-Pad22)") (class "Default")
      (node (ref "MPU6050-1") (pin "22") (pinfunction "RESV2_22") (pintype "bidirectional"))
    )
    (net (code "84") (name "unconnected-(U2-DCC-Pad47)") (class "Default")
      (node (ref "U2") (pin "47") (pinfunction "DCC_47") (pintype "bidirectional"))
    )
    (net (code "85") (name "unconnected-(U2-DEC2-Pad32)") (class "Default")
      (node (ref "U2") (pin "32") (pinfunction "DEC2_32") (pintype "bidirectional"))
    )
    (net (code "86") (name "unconnected-(U2-P0.02-Pad4)") (class "Default")
      (node (ref "U2") (pin "4") (pinfunction "P0.02_4") (pintype "bidirectional"))
    )
    (net (code "87") (name "unconnected-(U2-P0.03-Pad5)") (class "Default")
      (node (ref "U2") (pin "5") (pinfunction "P0.03_5") (pintype "bidirectional"))
    )
    (net (code "88") (name "unconnected-(U2-P0.04-Pad6)") (class "Default")
      (node (ref "U2") (pin "6") (pinfunction "P0.04_6") (pintype "bidirectional"))
    )
    (net (code "89") (name "unconnected-(U2-P0.05-Pad7)") (class "Default")
      (node (ref "U2") (pin "7") (pinfunction "P0.05_7") (pintype "bidirectional"))
    )
    (net (code "90") (name "unconnected-(U2-P0.06-Pad8)") (class "Default")
      (node (ref "U2") (pin "8") (pinfunction "P0.06_8") (pintype "bidirectional"))
    )
    (net (code "91") (name "unconnected-(U2-P0.07-Pad9)") (class "Default")
      (node (ref "U2") (pin "9") (pinfunction "P0.07_9") (pintype "bidirectional"))
    )
    (net (code "92") (name "unconnected-(U2-P0.08-Pad10)") (class "Default")
      (node (ref "U2") (pin "10") (pinfunction "P0.08_10") (pintype "bidirectional"))
    )
    (net (code "93") (name "unconnected-(U2-P0.09-Pad11)") (class "Default")
      (node (ref "U2") (pin "11") (pinfunction "P0.09_11") (pintype "bidirectional"))
    )
    (net (code "94") (name "unconnected-(U2-P0.10-Pad12)") (class "Default")
      (node (ref "U2") (pin "12") (pinfunction "P0.10_12") (pintype "bidirectional"))
    )
    (net (code "95") (name "unconnected-(U2-P0.11-Pad14)") (class "Default")
      (node (ref "U2") (pin "14") (pinfunction "P0.11_14") (pintype "bidirectional"))
    )
    (net (code "96") (name "unconnected-(U2-P0.12-Pad15)") (class "Default")
      (node (ref "U2") (pin "15") (pinfunction "P0.12_15") (pintype "bidirectional"))
    )
    (net (code "97") (name "unconnected-(U2-P0.13-Pad16)") (class "Default")
      (node (ref "U2") (pin "16") (pinfunction "P0.13_16") (pintype "bidirectional"))
    )
    (net (code "98") (name "unconnected-(U2-P0.17-Pad20)") (class "Default")
      (node (ref "U2") (pin "20") (pinfunction "P0.17_20") (pintype "bidirectional"))
    )
    (net (code "99") (name "unconnected-(U2-P0.19-Pad22)") (class "Default")
      (node (ref "U2") (pin "22") (pinfunction "P0.19_22") (pintype "bidirectional"))
    )
    (net (code "100") (name "unconnected-(U2-P0.20-Pad23)") (class "Default")
      (node (ref "U2") (pin "23") (pinfunction "P0.20_23") (pintype "bidirectional"))
    )
    (net (code "101") (name "unconnected-(U2-P0.22-Pad27)") (class "Default")
      (node (ref "U2") (pin "27") (pinfunction "P0.22_27") (pintype "bidirectional"))
    )
    (net (code "102") (name "unconnected-(U2-P0.23-Pad28)") (class "Default")
      (node (ref "U2") (pin "28") (pinfunction "P0.23_28") (pintype "bidirectional"))
    )
    (net (code "103") (name "unconnected-(U2-P0.24-Pad29)") (class "Default")
      (node (ref "U2") (pin "29") (pinfunction "P0.24_29") (pintype "bidirectional"))
    )
    (net (code "104") (name "unconnected-(U2-P0.25-Pad37)") (class "Default")
      (node (ref "U2") (pin "37") (pinfunction "P0.25_37") (pintype "bidirectional"))
    )
    (net (code "105") (name "unconnected-(U2-P0.26-Pad38)") (class "Default")
      (node (ref "U2") (pin "38") (pinfunction "P0.26_38") (pintype "bidirectional"))
    )
    (net (code "106") (name "unconnected-(U2-P0.27-Pad39)") (class "Default")
      (node (ref "U2") (pin "39") (pinfunction "P0.27_39") (pintype "bidirectional"))
    )
    (net (code "107") (name "unconnected-(U2-P0.28-Pad40)") (class "Default")
      (node (ref "U2") (pin "40") (pinfunction "P0.28_40") (pintype "bidirectional"))
    )
    (net (code "108") (name "unconnected-(U2-P0.29-Pad41)") (class "Default")
      (node (ref "U2") (pin "41") (pinfunction "P0.29_41") (pintype "bidirectional"))
    )
    (net (code "109") (name "unconnected-(U2-P0.30-Pad42)") (class "Default")
      (node (ref "U2") (pin "42") (pinfunction "P0.30_42") (pintype "bidirectional"))
    )
    (net (code "110") (name "unconnected-(U2-P0.31-Pad43)") (class "Default")
      (node (ref "U2") (pin "43") (pinfunction "P0.31_43") (pintype "bidirectional"))
    )
    (net (code "111") (name "unconnected-(U2-RESET-Pad24)") (class "Default")
      (node (ref "U2") (pin "24") (pinfunction "RESET_24") (pintype "bidirectional"))
    )
    (net (code "112") (name "unconnected-(U2-SWDCLK-Pad25)") (class "Default")
      (node (ref "U2") (pin "25") (pinfunction "SWDCLK_25") (pintype "bidirectional"))
    )
    (net (code "113") (name "unconnected-(U2-SWDIO-Pad26)") (class "Default")
      (node (ref "U2") (pin "26") (pinfunction "SWDIO_26") (pintype "bidirectional"))
    )
    (net (code "114") (name "unconnected-(U2-VSS2-Pad44)") (class "Default")
      (node (ref "U2") (pin "44") (pinfunction "VSS2_44") (pintype "bidirectional"))
    )
    (net (code "115") (name "unconnected-(U2-XL1-Pad2)") (class "Default")
      (node (ref "U2") (pin "2") (pinfunction "XL1_2") (pintype "bidirectional"))
    )
    (net (code "116") (name "unconnected-(U2-XL2-Pad3)") (class "Default")
      (node (ref "U2") (pin "3") (pinfunction "XL2_3") (pintype "bidirectional"))
    )
    (net (code "117") (name "unconnected-(USB1-ID-Pad4)") (class "Default")
      (node (ref "USB1") (pin "4") (pinfunction "ID_4") (pintype "bidirectional"))
    )
  )
)
